# MCU_ESC.net
KiCad netlist of a schematic drawn in Altium Designer
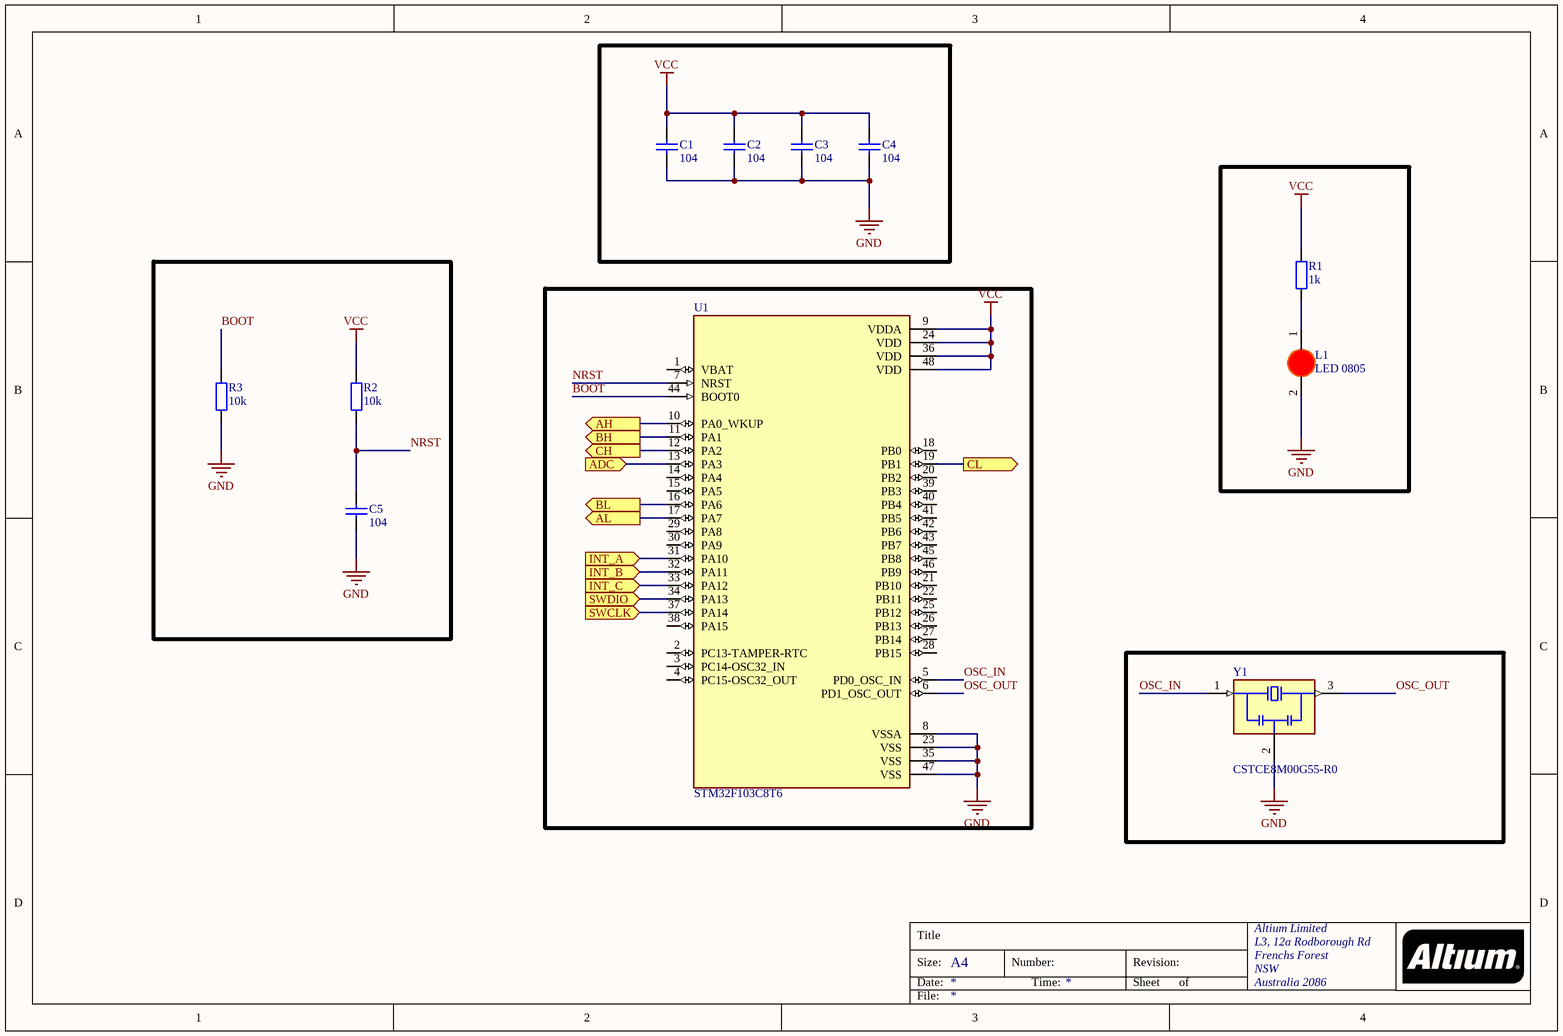
[diagram p0: MCU_ESC.SchDoc]

(export (version "E")
  (design (tool "Eeschema 10.0.6"))
  (components
    (comp (ref "C1")
      (value "104")
      (footprint "tu 0805")
      (description "Dán")
      (libsource (lib "Tu dien") (part "Tu 0805 104 50V 10%"))
    )
    (comp (ref "C2")
      (value "104")
      (footprint "tu 0805")
      (description "Dán")
      (libsource (lib "Tu dien") (part "Tu 0805 104 50V 10%"))
    )
    (comp (ref "C3")
      (value "104")
      (footprint "tu 0805")
      (description "Dán")
      (libsource (lib "Tu dien") (part "Tu 0805 104 50V 10%"))
    )
    (comp (ref "C4")
      (value "104")
      (footprint "tu 0805")
      (description "Dán")
      (libsource (lib "Tu dien") (part "Tu 0805 104 50V 10%"))
    )
    (comp (ref "C5")
      (value "104")
      (footprint "tu 0805")
      (description "Dán")
      (libsource (lib "Tu dien") (part "Tu 0805 104 50V 10%"))
    )
    (comp (ref "L1")
      (value "LED 0805")
      (footprint "LED-0805-Red")
      (description "Dán")
      (libsource (lib "Led") (part "LED 0805 Do"))
    )
    (comp (ref "R1")
      (value "1k")
      (footprint "tro smd 0603")
      (description "Dán")
      (libsource (lib "Dien Tro") (part "Tro 0603 1% 1k"))
    )
    (comp (ref "R2")
      (value "10k")
      (footprint "tro smd 0805")
      (description "Dán")
      (libsource (lib "Dien Tro") (part "Tro 0805 1% 10k"))
    )
    (comp (ref "R3")
      (value "10k")
      (footprint "tro smd 0805")
      (description "Dán")
      (libsource (lib "Dien Tro") (part "Tro 0805 1% 10k"))
    )
    (comp (ref "U1")
      (value "STM32F103C8T6")
      (footprint "QFP50P900X900X160-48N")
      (description "ARMÂ® CortexÂ®-M3 STM32F1 Microcontroller IC 32-Bit 72MHz 64KB (64K x 8) FLASH 48-LQFP (7x7)")
      (fields (field (name "MF") "STMicroelectronics"))
      (libsource (lib "STM32F103C8T6") (part "STM32F103C8T6"))
    )
    (comp (ref "Y1")
      (value "CSTCE8M00G55-R0")
      (footprint "OSC_CSTCE8M00G55-R0")
      (description "8 MHz Ceramic Resonator Built in Capacitor 33 pF Â±0.2% -20Â°C ~ 80Â°C Surface Mount")
      (fields (field (name "MF") "Murata"))
      (libsource (lib "CSTCE8M00G55-R0") (part "CSTCE8M00G55-R0"))
    )
  )
  (nets
    (net (code "1") (name "/ADC") (class "Default")
      (node (ref "U1") (pin "13") (pinfunction "PA3_13") (pintype "bidirectional"))
    )
    (net (code "2") (name "/AH") (class "Default")
      (node (ref "U1") (pin "10") (pinfunction "PA0_WKUP_10") (pintype "bidirectional"))
    )
    (net (code "3") (name "/AL") (class "Default")
      (node (ref "U1") (pin "17") (pinfunction "PA7_17") (pintype "bidirectional"))
    )
    (net (code "4") (name "/BH") (class "Default")
      (node (ref "U1") (pin "11") (pinfunction "PA1_11") (pintype "bidirectional"))
    )
    (net (code "5") (name "/BL") (class "Default")
      (node (ref "U1") (pin "16") (pinfunction "PA6_16") (pintype "bidirectional"))
    )
    (net (code "6") (name "/BOOT") (class "Default")
      (node (ref "R3") (pin "2") (pinfunction "2_2") (pintype "passive"))
      (node (ref "U1") (pin "44") (pinfunction "BOOT0_44") (pintype "input"))
    )
    (net (code "7") (name "/CH") (class "Default")
      (node (ref "U1") (pin "12") (pinfunction "PA2_12") (pintype "bidirectional"))
    )
    (net (code "8") (name "/CL") (class "Default")
      (node (ref "U1") (pin "19") (pinfunction "PB1_19") (pintype "bidirectional"))
    )
    (net (code "9") (name "/INT_A") (class "Default")
      (node (ref "U1") (pin "31") (pinfunction "PA10_31") (pintype "bidirectional"))
    )
    (net (code "10") (name "/INT_B") (class "Default")
      (node (ref "U1") (pin "32") (pinfunction "PA11_32") (pintype "bidirectional"))
    )
    (net (code "11") (name "/INT_C") (class "Default")
      (node (ref "U1") (pin "33") (pinfunction "PA12_33") (pintype "bidirectional"))
    )
    (net (code "12") (name "/NRST") (class "Default")
      (node (ref "C5") (pin "1") (pinfunction "1_1") (pintype "passive"))
      (node (ref "R2") (pin "1") (pinfunction "1_1") (pintype "passive"))
      (node (ref "U1") (pin "7") (pinfunction "NRST_7") (pintype "input"))
    )
    (net (code "13") (name "/OSC_IN") (class "Default")
      (node (ref "U1") (pin "5") (pinfunction "PD0_OSC_IN_5") (pintype "bidirectional"))
      (node (ref "Y1") (pin "1") (pinfunction "IN_1") (pintype "input"))
    )
    (net (code "14") (name "/OSC_OUT") (class "Default")
      (node (ref "U1") (pin "6") (pinfunction "PD1_OSC_OUT_6") (pintype "bidirectional"))
      (node (ref "Y1") (pin "3") (pinfunction "OUT_3") (pintype "output"))
    )
    (net (code "15") (name "/SWCLK") (class "Default")
      (node (ref "U1") (pin "37") (pinfunction "PA14_37") (pintype "bidirectional"))
    )
    (net (code "16") (name "/SWDIO") (class "Default")
      (node (ref "U1") (pin "34") (pinfunction "PA13_34") (pintype "bidirectional"))
    )
    (net (code "17") (name "GND") (class "Default")
      (node (ref "C1") (pin "2") (pinfunction "2_2") (pintype "passive"))
      (node (ref "C2") (pin "2") (pinfunction "2_2") (pintype "passive"))
      (node (ref "C3") (pin "2") (pinfunction "2_2") (pintype "passive"))
      (node (ref "C4") (pin "2") (pinfunction "2_2") (pintype "passive"))
      (node (ref "C5") (pin "2") (pinfunction "2_2") (pintype "passive"))
      (node (ref "L1") (pin "2") (pinfunction "K_2") (pintype "passive"))
      (node (ref "R3") (pin "1") (pinfunction "1_1") (pintype "passive"))
      (node (ref "U1") (pin "23") (pinfunction "VSS_23") (pintype "power_in"))
      (node (ref "U1") (pin "35") (pinfunction "VSS_35") (pintype "power_in"))
      (node (ref "U1") (pin "47") (pinfunction "VSS_47") (pintype "power_in"))
      (node (ref "U1") (pin "8") (pinfunction "VSSA_8") (pintype "power_in"))
      (node (ref "Y1") (pin "2") (pinfunction "GND_2") (pintype "power_in"))
    )
    (net (code "18") (name "Net-(L1-A)") (class "Default")
      (node (ref "L1") (pin "1") (pinfunction "A_1") (pintype "passive"))
      (node (ref "R1") (pin "1") (pinfunction "1_1") (pintype "passive"))
    )
    (net (code "19") (name "VCC") (class "Default")
      (node (ref "C1") (pin "1") (pinfunction "1_1") (pintype "passive"))
      (node (ref "C2") (pin "1") (pinfunction "1_1") (pintype "passive"))
      (node (ref "C3") (pin "1") (pinfunction "1_1") (pintype "passive"))
      (node (ref "C4") (pin "1") (pinfunction "1_1") (pintype "passive"))
      (node (ref "R1") (pin "2") (pinfunction "2_2") (pintype "passive"))
      (node (ref "R2") (pin "2") (pinfunction "2_2") (pintype "passive"))
      (node (ref "U1") (pin "24") (pinfunction "VDD_24") (pintype "power_in"))
      (node (ref "U1") (pin "36") (pinfunction "VDD_36") (pintype "power_in"))
      (node (ref "U1") (pin "48") (pinfunction "VDD_48") (pintype "power_in"))
      (node (ref "U1") (pin "9") (pinfunction "VDDA_9") (pintype "power_in"))
    )
    (net (code "20") (name "unconnected-(U1-PA4-Pad14)") (class "Default")
      (node (ref "U1") (pin "14") (pinfunction "PA4_14") (pintype "bidirectional"))
    )
    (net (code "21") (name "unconnected-(U1-PA5-Pad15)") (class "Default")
      (node (ref "U1") (pin "15") (pinfunction "PA5_15") (pintype "bidirectional"))
    )
    (net (code "22") (name "unconnected-(U1-PA8-Pad29)") (class "Default")
      (node (ref "U1") (pin "29") (pinfunction "PA8_29") (pintype "bidirectional"))
    )
    (net (code "23") (name "unconnected-(U1-PA9-Pad30)") (class "Default")
      (node (ref "U1") (pin "30") (pinfunction "PA9_30") (pintype "bidirectional"))
    )
    (net (code "24") (name "unconnected-(U1-PA15-Pad38)") (class "Default")
      (node (ref "U1") (pin "38") (pinfunction "PA15_38") (pintype "bidirectional"))
    )
    (net (code "25") (name "unconnected-(U1-PB0-Pad18)") (class "Default")
      (node (ref "U1") (pin "18") (pinfunction "PB0_18") (pintype "bidirectional"))
    )
    (net (code "26") (name "unconnected-(U1-PB2-Pad20)") (class "Default")
      (node (ref "U1") (pin "20") (pinfunction "PB2_20") (pintype "bidirectional"))
    )
    (net (code "27") (name "unconnected-(U1-PB3-Pad39)") (class "Default")
      (node (ref "U1") (pin "39") (pinfunction "PB3_39") (pintype "bidirectional"))
    )
    (net (code "28") (name "unconnected-(U1-PB4-Pad40)") (class "Default")
      (node (ref "U1") (pin "40") (pinfunction "PB4_40") (pintype "bidirectional"))
    )
    (net (code "29") (name "unconnected-(U1-PB5-Pad41)") (class "Default")
      (node (ref "U1") (pin "41") (pinfunction "PB5_41") (pintype "bidirectional"))
    )
    (net (code "30") (name "unconnected-(U1-PB6-Pad42)") (class "Default")
      (node (ref "U1") (pin "42") (pinfunction "PB6_42") (pintype "bidirectional"))
    )
    (net (code "31") (name "unconnected-(U1-PB7-Pad43)") (class "Default")
      (node (ref "U1") (pin "43") (pinfunction "PB7_43") (pintype "bidirectional"))
    )
    (net (code "32") (name "unconnected-(U1-PB8-Pad45)") (class "Default")
      (node (ref "U1") (pin "45") (pinfunction "PB8_45") (pintype "bidirectional"))
    )
    (net (code "33") (name "unconnected-(U1-PB9-Pad46)") (class "Default")
      (node (ref "U1") (pin "46") (pinfunction "PB9_46") (pintype "bidirectional"))
    )
    (net (code "34") (name "unconnected-(U1-PB10-Pad21)") (class "Default")
      (node (ref "U1") (pin "21") (pinfunction "PB10_21") (pintype "bidirectional"))
    )
    (net (code "35") (name "unconnected-(U1-PB11-Pad22)") (class "Default")
      (node (ref "U1") (pin "22") (pinfunction "PB11_22") (pintype "bidirectional"))
    )
    (net (code "36") (name "unconnected-(U1-PB12-Pad25)") (class "Default")
      (node (ref "U1") (pin "25") (pinfunction "PB12_25") (pintype "bidirectional"))
    )
    (net (code "37") (name "unconnected-(U1-PB13-Pad26)") (class "Default")
      (node (ref "U1") (pin "26") (pinfunction "PB13_26") (pintype "bidirectional"))
    )
    (net (code "38") (name "unconnected-(U1-PB14-Pad27)") (class "Default")
      (node (ref "U1") (pin "27") (pinfunction "PB14_27") (pintype "bidirectional"))
    )
    (net (code "39") (name "unconnected-(U1-PB15-Pad28)") (class "Default")
      (node (ref "U1") (pin "28") (pinfunction "PB15_28") (pintype "bidirectional"))
    )
    (net (code "40") (name "unconnected-(U1-PC13-TAMPER-RTC-Pad2)") (class "Default")
      (node (ref "U1") (pin "2") (pinfunction "PC13-TAMPER-RTC_2") (pintype "bidirectional"))
    )
    (net (code "41") (name "unconnected-(U1-PC14-OSC32_IN-Pad3)") (class "Default")
      (node (ref "U1") (pin "3") (pinfunction "PC14-OSC32_IN_3") (pintype "bidirectional"))
    )
    (net (code "42") (name "unconnected-(U1-PC15-OSC32_OUT-Pad4)") (class "Default")
      (node (ref "U1") (pin "4") (pinfunction "PC15-OSC32_OUT_4") (pintype "bidirectional"))
    )
    (net (code "43") (name "unconnected-(U1-VBAT-Pad1)") (class "Default")
      (node (ref "U1") (pin "1") (pinfunction "VBAT_1") (pintype "bidirectional"))
    )
  )
)
